# User_-_User_Led_s.net
KiCad netlist of a schematic drawn in Altium Designer
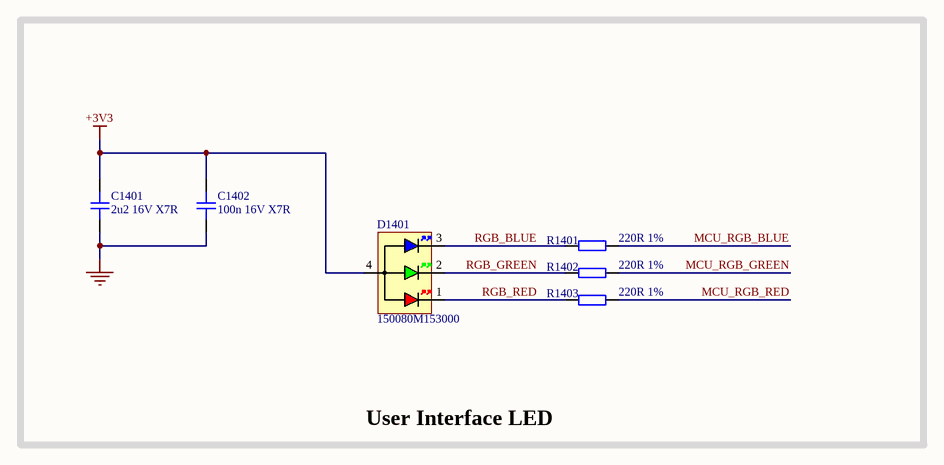
[diagram p0: User - User Led's.SchDoc]

(export (version "E")
  (design (tool "Eeschema 10.0.6"))
  (components
    (comp (ref "C1401")
      (value "2u2 16V X7R")
      (footprint "CAP_0603")
      (description "Capacitor SMD 0603")
      (fields
        (field (name "MANUFACTURER") "YAGEO")
        (field (name "MANUFACTURER PART NUMBER") "CC0603KRX7R7BB225")
      )
      (libsource (lib "Schematic-Lib-PhilsLab") (part "CAP_0603"))
    )
    (comp (ref "C1402")
      (value "100n 16V X7R")
      (footprint "CAP_0402")
      (description "Capacitor SMD 0402")
      (fields
        (field (name "MANUFACTURER") "YAGEO")
        (field (name "MANUFACTURER PART NUMBER") "CC0402JRX7R7BB104")
      )
      (libsource (lib "Schematic-Lib-PhilsLab") (part "CAP_0402"))
    )
    (comp (ref "D1401")
      (value "150080M153000")
      (footprint "150080M153000")
      (description "RGB LED Common Anode SMD Diffused 0805 Top View")
      (fields (field (name "MANUFACTURER") "Wurth"))
      (libsource (lib "Schematic-Lib") (part "150080M153000"))
    )
    (comp (ref "R1401")
      (value "220R 1%")
      (footprint "RES_0402")
      (description "Resistor SMD 0402")
      (fields
        (field (name "MANUFACTURER") "PANASONIC")
        (field (name "MANUFACTURER PART NUMBER") "ERJPA2F1002X")
      )
      (libsource (lib "Schematic-Lib-PhilsLab") (part "RES_0402"))
    )
    (comp (ref "R1402")
      (value "220R 1%")
      (footprint "RES_0402")
      (description "Resistor SMD 0402")
      (fields
        (field (name "MANUFACTURER") "PANASONIC")
        (field (name "MANUFACTURER PART NUMBER") "ERJPA2F1002X")
      )
      (libsource (lib "Schematic-Lib-PhilsLab") (part "RES_0402"))
    )
    (comp (ref "R1403")
      (value "220R 1%")
      (footprint "RES_0402")
      (description "Resistor SMD 0402")
      (fields
        (field (name "MANUFACTURER") "PANASONIC")
        (field (name "MANUFACTURER PART NUMBER") "ERJPA2F1002X")
      )
      (libsource (lib "Schematic-Lib-PhilsLab") (part "RES_0402"))
    )
  )
  (nets
    (net (code "1") (name "+3V3") (class "Default")
      (node (ref "C1401") (pin "2") (pinfunction "2_2") (pintype "passive"))
      (node (ref "C1402") (pin "2") (pinfunction "2_2") (pintype "passive"))
      (node (ref "D1401") (pin "4") (pinfunction "AC_4") (pintype "passive"))
    )
    (net (code "2") (name "/MCU_RGB_BLUE") (class "Default")
      (node (ref "R1401") (pin "1") (pinfunction "1_1") (pintype "passive"))
    )
    (net (code "3") (name "/MCU_RGB_GREEN") (class "Default")
      (node (ref "R1402") (pin "1") (pinfunction "1_1") (pintype "passive"))
    )
    (net (code "4") (name "/MCU_RGB_RED") (class "Default")
      (node (ref "R1403") (pin "1") (pinfunction "1_1") (pintype "passive"))
    )
    (net (code "5") (name "/RGB_BLUE") (class "Default")
      (node (ref "D1401") (pin "3") (pinfunction "CB_3") (pintype "passive"))
      (node (ref "R1401") (pin "2") (pinfunction "2_2") (pintype "passive"))
    )
    (net (code "6") (name "/RGB_GREEN") (class "Default")
      (node (ref "D1401") (pin "2") (pinfunction "CG_2") (pintype "passive"))
      (node (ref "R1402") (pin "2") (pinfunction "2_2") (pintype "passive"))
    )
    (net (code "7") (name "/RGB_RED") (class "Default")
      (node (ref "D1401") (pin "1") (pinfunction "CR_1") (pintype "passive"))
      (node (ref "R1403") (pin "2") (pinfunction "2_2") (pintype "passive"))
    )
    (net (code "8") (name "GND") (class "Default")
      (node (ref "C1401") (pin "1") (pinfunction "1_1") (pintype "passive"))
      (node (ref "C1402") (pin "1") (pinfunction "1_1") (pintype "passive"))
    )
  )
)
